# ecu.net
KiCad netlist of a schematic drawn in EAGLE
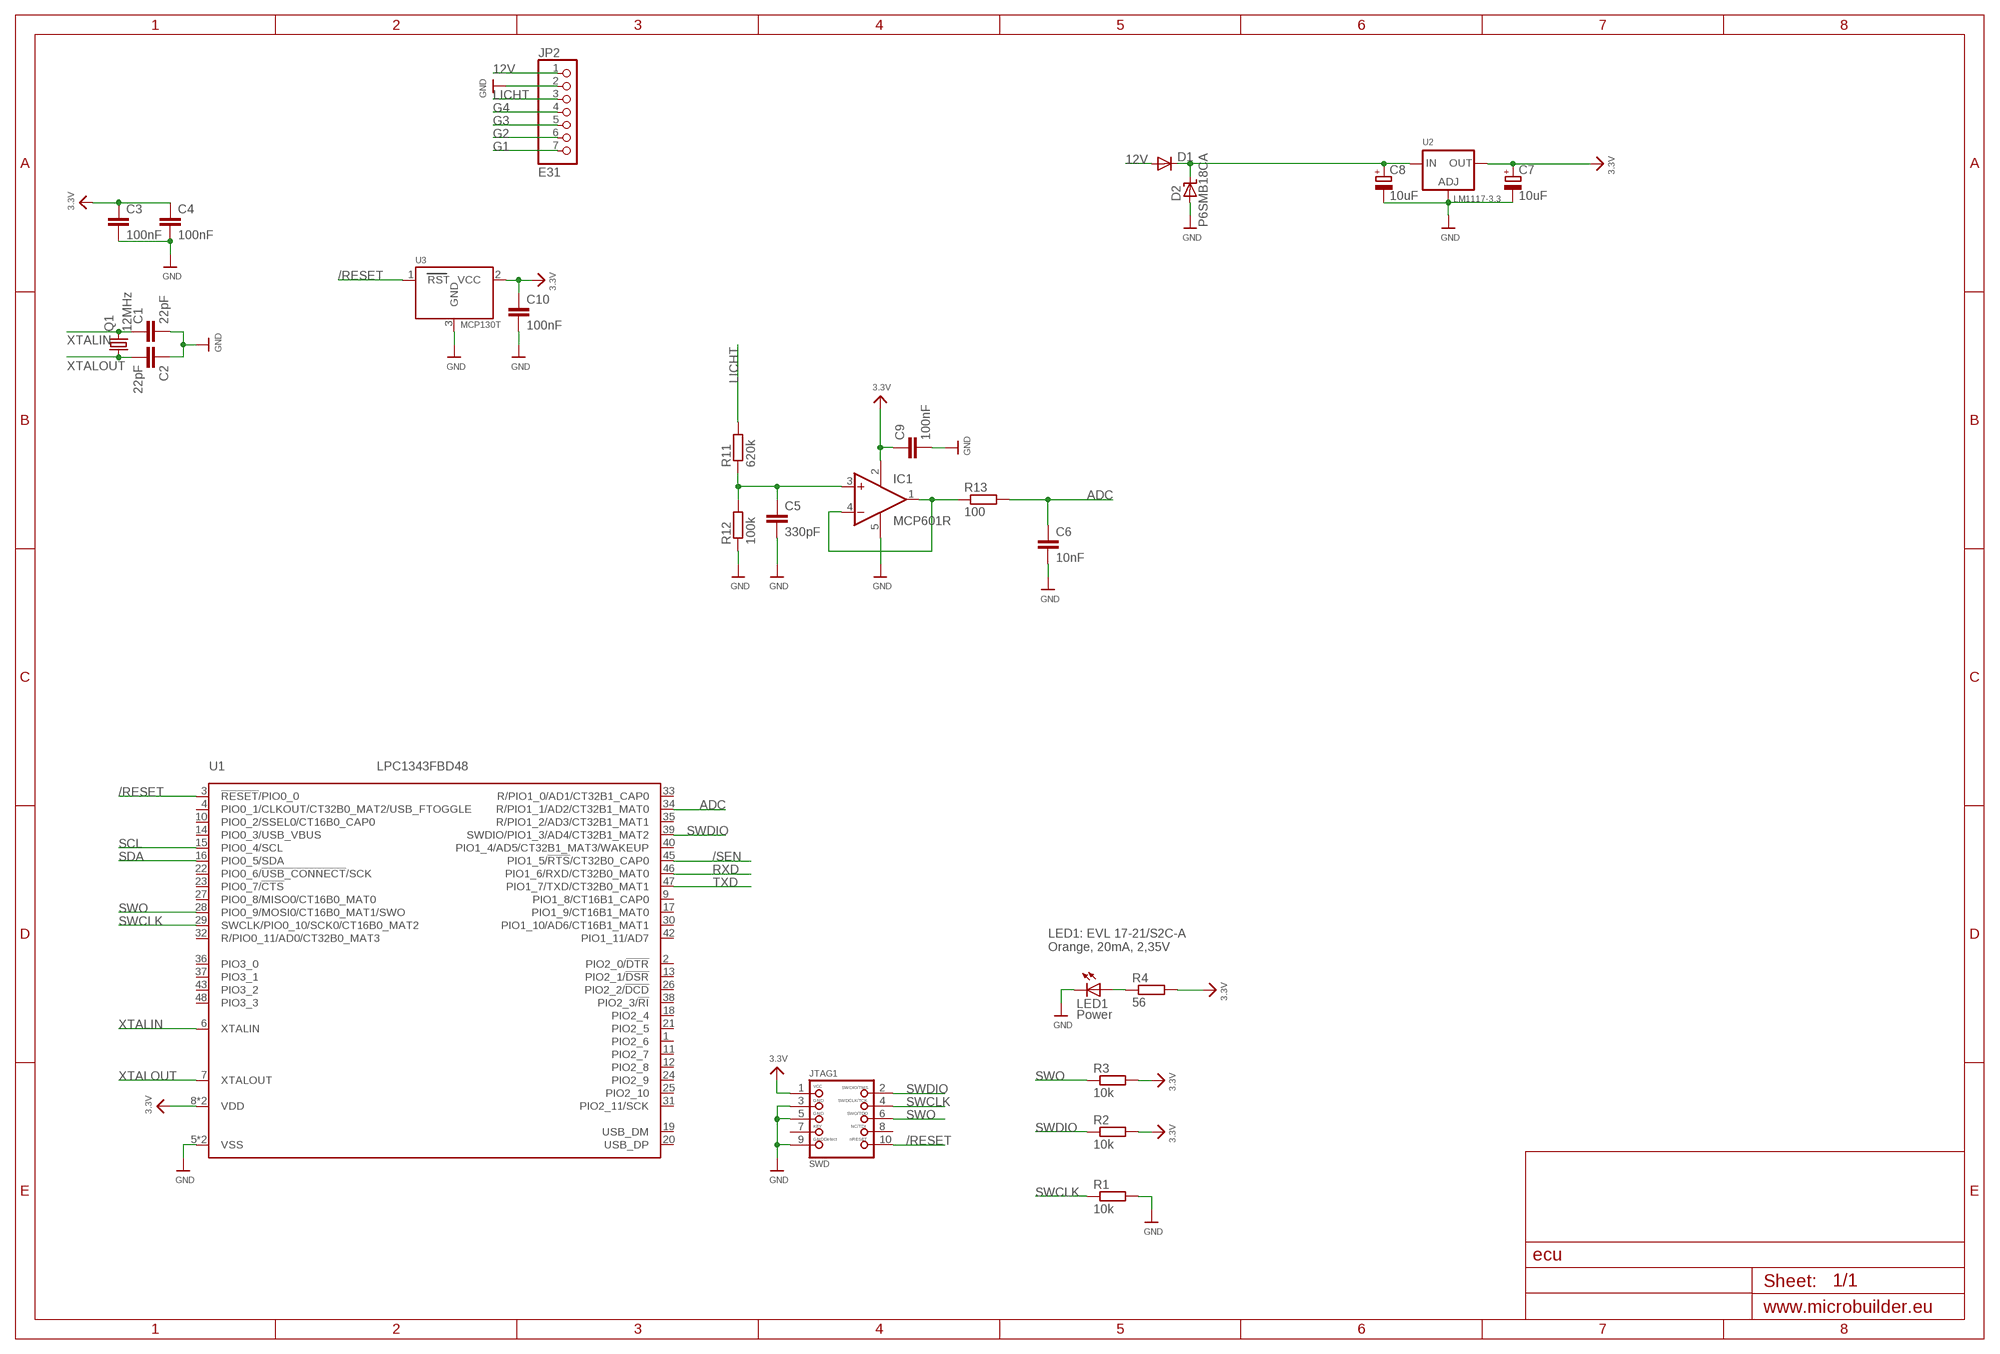
[diagram p0: schematic, sheet 1]

(export (version "E")
  (design (tool "Eeschema 10.0.6"))
  (components
    (comp (ref "C1")
      (value "22pF")
      (footprint "eagle-import:C0805")
      (libsource (lib "eagle-import") (part "C-EUC0805"))
    )
    (comp (ref "C2")
      (value "22pF")
      (footprint "eagle-import:C0805")
      (libsource (lib "eagle-import") (part "C-EUC0805"))
    )
    (comp (ref "C3")
      (value "100nF")
      (footprint "eagle-import:C0805")
      (libsource (lib "eagle-import") (part "C-EUC0805"))
    )
    (comp (ref "C4")
      (value "100nF")
      (footprint "eagle-import:C0805")
      (libsource (lib "eagle-import") (part "C-EUC0805"))
    )
    (comp (ref "C5")
      (value "330pF")
      (footprint "eagle-import:C0805")
      (libsource (lib "eagle-import") (part "C-EUC0805"))
    )
    (comp (ref "C6")
      (value "10nF")
      (footprint "eagle-import:C0805")
      (libsource (lib "eagle-import") (part "C-EUC0805"))
    )
    (comp (ref "C7")
      (value "10uF")
      (footprint "eagle-import:SMC_C")
      (libsource (lib "eagle-import") (part "CPOL-EUSMCC"))
    )
    (comp (ref "C8")
      (value "10uF")
      (footprint "eagle-import:SMC_C")
      (libsource (lib "eagle-import") (part "CPOL-EUSMCC"))
    )
    (comp (ref "C9")
      (value "100nF")
      (footprint "eagle-import:C0805")
      (libsource (lib "eagle-import") (part "rcl_334_C-EUC0805"))
    )
    (comp (ref "C10")
      (value "100nF")
      (footprint "eagle-import:C0805")
      (libsource (lib "eagle-import") (part "rcl_334_C-EUC0805"))
    )
    (comp (ref "D1")
      (value "DIODE-SMB")
      (footprint "eagle-import:SMB")
      (libsource (lib "eagle-import") (part "DIODE-SMB"))
    )
    (comp (ref "D2")
      (value "P6SMB18CA")
      (footprint "eagle-import:DO214AA")
      (libsource (lib "eagle-import") (part "SHOTKY-SMDSMB"))
    )
    (comp (ref "IC1")
      (value "MCP601R")
      (footprint "eagle-import:SOT23-5")
      (libsource (lib "eagle-import") (part "MCP601R"))
    )
    (comp (ref "JP2")
      (value "E31")
      (footprint "eagle-import:1X07_ROUND")
      (libsource (lib "eagle-import") (part "HEADER-1X7ROUND"))
    )
    (comp (ref "JTAG1")
      (value "SWD")
      (footprint "eagle-import:2X05_1.27MM_SMT")
      (libsource (lib "eagle-import") (part "JTAG-CORTEXM3"))
    )
    (comp (ref "LED1")
      (value "Power")
      (footprint "eagle-import:SML0805")
      (libsource (lib "eagle-import") (part "LEDSML0805"))
    )
    (comp (ref "Q1")
      (value "12MHz")
      (footprint "eagle-import:HC49UP")
      (libsource (lib "eagle-import") (part "CRYSTALHC49UP"))
    )
    (comp (ref "R1")
      (value "10k")
      (footprint "eagle-import:R0805")
      (libsource (lib "eagle-import") (part "rcl_334_R-EU_R0805"))
    )
    (comp (ref "R2")
      (value "10k")
      (footprint "eagle-import:R0805")
      (libsource (lib "eagle-import") (part "rcl_334_R-EU_R0805"))
    )
    (comp (ref "R3")
      (value "10k")
      (footprint "eagle-import:R0805")
      (libsource (lib "eagle-import") (part "rcl_334_R-EU_R0805"))
    )
    (comp (ref "R4")
      (value "56")
      (footprint "eagle-import:R0805")
      (libsource (lib "eagle-import") (part "rcl_334_R-EU_R0805"))
    )
    (comp (ref "R11")
      (value "620k")
      (footprint "eagle-import:R0805")
      (libsource (lib "eagle-import") (part "R-EU_R0805"))
    )
    (comp (ref "R12")
      (value "100k")
      (footprint "eagle-import:R0805")
      (libsource (lib "eagle-import") (part "R-EU_R0805"))
    )
    (comp (ref "R13")
      (value "100")
      (footprint "eagle-import:R0805")
      (libsource (lib "eagle-import") (part "R-EU_R0805"))
    )
    (comp (ref "U1")
      (value "LPC1343FBD48")
      (footprint "eagle-import:SOT313-2")
      (libsource (lib "eagle-import") (part "LPC1343FBD48"))
    )
    (comp (ref "U2")
      (value "LM1117-3.3")
      (footprint "eagle-import:SOT223-R")
      (libsource (lib "eagle-import") (part "LM1117SOT223-REFLOW"))
    )
    (comp (ref "U3")
      (value "MCP130T")
      (footprint "eagle-import:SOT23-W")
      (libsource (lib "eagle-import") (part "MCP130TWAVE"))
    )
  )
  (nets
    (net (code "1") (name "/12V") (class "Default")
      (node (ref "D1") (pin "A") (pinfunction "A_A") (pintype "passive"))
      (node (ref "JP2") (pin "1") (pinfunction "1_1") (pintype "passive"))
    )
    (net (code "2") (name "/ADC") (class "Default")
      (node (ref "C6") (pin "1") (pinfunction "1_1") (pintype "passive"))
      (node (ref "R13") (pin "2") (pinfunction "2_2") (pintype "passive"))
      (node (ref "U1") (pin "34") (pinfunction "R/PIO1_1/AD2/CT32B1_MAT0_34") (pintype "bidirectional"))
    )
    (net (code "3") (name "/G1") (class "Default")
      (node (ref "JP2") (pin "7") (pinfunction "7_7") (pintype "passive"))
    )
    (net (code "4") (name "/G2") (class "Default")
      (node (ref "JP2") (pin "6") (pinfunction "6_6") (pintype "passive"))
    )
    (net (code "5") (name "/G3") (class "Default")
      (node (ref "JP2") (pin "5") (pinfunction "5_5") (pintype "passive"))
    )
    (net (code "6") (name "/G4") (class "Default")
      (node (ref "JP2") (pin "4") (pinfunction "4_4") (pintype "passive"))
    )
    (net (code "7") (name "/LICHT") (class "Default")
      (node (ref "JP2") (pin "3") (pinfunction "3_3") (pintype "passive"))
      (node (ref "R11") (pin "2") (pinfunction "2_2") (pintype "passive"))
    )
    (net (code "8") (name "/RXD") (class "Default")
      (node (ref "U1") (pin "46") (pinfunction "PIO1_6/RXD/CT32B0_MAT0_46") (pintype "bidirectional"))
    )
    (net (code "9") (name "/SCL") (class "Default")
      (node (ref "U1") (pin "15") (pinfunction "PIO0_4/SCL_15") (pintype "bidirectional"))
    )
    (net (code "10") (name "/SDA") (class "Default")
      (node (ref "U1") (pin "16") (pinfunction "PIO0_5/SDA_16") (pintype "bidirectional"))
    )
    (net (code "11") (name "/SWCLK") (class "Default")
      (node (ref "JTAG1") (pin "4") (pinfunction "4_4") (pintype "passive"))
      (node (ref "R1") (pin "1") (pinfunction "1_1") (pintype "passive"))
      (node (ref "U1") (pin "29") (pinfunction "SWCLK/PIO0_10/SCK0/CT16B0_MAT2_29") (pintype "bidirectional"))
    )
    (net (code "12") (name "/SWDIO") (class "Default")
      (node (ref "JTAG1") (pin "2") (pinfunction "2_2") (pintype "passive"))
      (node (ref "R2") (pin "1") (pinfunction "1_1") (pintype "passive"))
      (node (ref "U1") (pin "39") (pinfunction "SWDIO/PIO1_3/AD4/CT32B1_MAT2_39") (pintype "bidirectional"))
    )
    (net (code "13") (name "/SWO") (class "Default")
      (node (ref "JTAG1") (pin "6") (pinfunction "6_6") (pintype "passive"))
      (node (ref "R3") (pin "1") (pinfunction "1_1") (pintype "passive"))
      (node (ref "U1") (pin "28") (pinfunction "PIO0_9/MOSI0/CT16B0_MAT1/SWO_28") (pintype "bidirectional"))
    )
    (net (code "14") (name "/TXD") (class "Default")
      (node (ref "U1") (pin "47") (pinfunction "PIO1_7/TXD/CT32B0_MAT1_47") (pintype "bidirectional"))
    )
    (net (code "15") (name "/XTALIN") (class "Default")
      (node (ref "C1") (pin "1") (pinfunction "1_1") (pintype "passive"))
      (node (ref "Q1") (pin "2") (pinfunction "2_2") (pintype "passive"))
      (node (ref "U1") (pin "6") (pinfunction "XTALIN_6") (pintype "input"))
    )
    (net (code "16") (name "/XTALOUT") (class "Default")
      (node (ref "C2") (pin "2") (pinfunction "2_2") (pintype "passive"))
      (node (ref "Q1") (pin "1") (pinfunction "1_1") (pintype "passive"))
      (node (ref "U1") (pin "7") (pinfunction "XTALOUT_7") (pintype "output"))
    )
    (net (code "17") (name "/{slash}RESET") (class "Default")
      (node (ref "JTAG1") (pin "10") (pinfunction "10_10") (pintype "passive"))
      (node (ref "U1") (pin "3") (pinfunction "~{RESET}/PIO0_0_3") (pintype "bidirectional"))
      (node (ref "U3") (pin "1") (pinfunction "RST_1") (pintype "bidirectional"))
    )
    (net (code "18") (name "/{slash}SEN") (class "Default")
      (node (ref "U1") (pin "45") (pinfunction "PIO1_5/~{RTS}/CT32B0_CAP0_45") (pintype "bidirectional"))
    )
    (net (code "19") (name "3.3V") (class "Default")
      (node (ref "C10") (pin "1") (pinfunction "1_1") (pintype "passive"))
      (node (ref "C3") (pin "1") (pinfunction "1_1") (pintype "passive"))
      (node (ref "C4") (pin "1") (pinfunction "1_1") (pintype "passive"))
      (node (ref "C7") (pin "+") (pinfunction "+_+") (pintype "passive"))
      (node (ref "C9") (pin "1") (pinfunction "1_1") (pintype "passive"))
      (node (ref "IC1") (pin "2") (pinfunction "V+_2") (pintype "power_in"))
      (node (ref "JTAG1") (pin "1") (pinfunction "1_1") (pintype "passive"))
      (node (ref "R2") (pin "2") (pinfunction "2_2") (pintype "passive"))
      (node (ref "R3") (pin "2") (pinfunction "2_2") (pintype "passive"))
      (node (ref "R4") (pin "2") (pinfunction "2_2") (pintype "passive"))
      (node (ref "U1") (pin "44") (pinfunction "VDD_44") (pintype "power_in"))
      (node (ref "U1") (pin "8") (pinfunction "VDD_8") (pintype "power_in"))
      (node (ref "U2") (pin "2") (pinfunction "OUT_2") (pintype "passive"))
      (node (ref "U3") (pin "2") (pinfunction "VCC_2") (pintype "power_in"))
    )
    (net (code "20") (name "GND") (class "Default")
      (node (ref "C1") (pin "2") (pinfunction "2_2") (pintype "passive"))
      (node (ref "C10") (pin "2") (pinfunction "2_2") (pintype "passive"))
      (node (ref "C2") (pin "1") (pinfunction "1_1") (pintype "passive"))
      (node (ref "C3") (pin "2") (pinfunction "2_2") (pintype "passive"))
      (node (ref "C4") (pin "2") (pinfunction "2_2") (pintype "passive"))
      (node (ref "C5") (pin "2") (pinfunction "2_2") (pintype "passive"))
      (node (ref "C6") (pin "2") (pinfunction "2_2") (pintype "passive"))
      (node (ref "C7") (pin "-") (pinfunction "-_-") (pintype "passive"))
      (node (ref "C8") (pin "-") (pinfunction "-_-") (pintype "passive"))
      (node (ref "C9") (pin "2") (pinfunction "2_2") (pintype "passive"))
      (node (ref "D2") (pin "A") (pinfunction "A_A") (pintype "passive"))
      (node (ref "IC1") (pin "5") (pinfunction "V-_5") (pintype "power_in"))
      (node (ref "JP2") (pin "2") (pinfunction "2_2") (pintype "passive"))
      (node (ref "JTAG1") (pin "3") (pinfunction "3_3") (pintype "passive"))
      (node (ref "JTAG1") (pin "5") (pinfunction "5_5") (pintype "passive"))
      (node (ref "JTAG1") (pin "9") (pinfunction "9_9") (pintype "passive"))
      (node (ref "LED1") (pin "C") (pinfunction "C_C") (pintype "passive"))
      (node (ref "R1") (pin "2") (pinfunction "2_2") (pintype "passive"))
      (node (ref "R12") (pin "1") (pinfunction "1_1") (pintype "passive"))
      (node (ref "U1") (pin "41") (pinfunction "VSS_41") (pintype "power_in"))
      (node (ref "U1") (pin "5") (pinfunction "VSS_5") (pintype "power_in"))
      (node (ref "U2") (pin "1") (pinfunction "ADJ_1") (pintype "input"))
      (node (ref "U3") (pin "3") (pinfunction "GND_3") (pintype "power_in"))
    )
    (net (code "21") (name "Net-(IC1-+IN)") (class "Default")
      (node (ref "C5") (pin "1") (pinfunction "1_1") (pintype "passive"))
      (node (ref "IC1") (pin "3") (pinfunction "+IN_3") (pintype "input"))
      (node (ref "R11") (pin "1") (pinfunction "1_1") (pintype "passive"))
      (node (ref "R12") (pin "2") (pinfunction "2_2") (pintype "passive"))
    )
    (net (code "22") (name "Net-(IC1--IN)") (class "Default")
      (node (ref "IC1") (pin "1") (pinfunction "OUT_1") (pintype "output"))
      (node (ref "IC1") (pin "4") (pinfunction "-IN_4") (pintype "input"))
      (node (ref "R13") (pin "1") (pinfunction "1_1") (pintype "passive"))
    )
    (net (code "23") (name "Net-(LED1-PadA)") (class "Default")
      (node (ref "LED1") (pin "A") (pinfunction "A_A") (pintype "passive"))
      (node (ref "R4") (pin "1") (pinfunction "1_1") (pintype "passive"))
    )
    (net (code "24") (name "Net-(U2-IN)") (class "Default")
      (node (ref "C8") (pin "+") (pinfunction "+_+") (pintype "passive"))
      (node (ref "D1") (pin "C") (pinfunction "C_C") (pintype "passive"))
      (node (ref "D2") (pin "C") (pinfunction "C_C") (pintype "passive"))
      (node (ref "U2") (pin "3") (pinfunction "IN_3") (pintype "input"))
    )
    (net (code "25") (name "unconnected-(JTAG1-Pad7)") (class "Default")
      (node (ref "JTAG1") (pin "7") (pinfunction "7_7") (pintype "passive"))
    )
    (net (code "26") (name "unconnected-(JTAG1-Pad8)") (class "Default")
      (node (ref "JTAG1") (pin "8") (pinfunction "8_8") (pintype "passive"))
    )
    (net (code "27") (name "unconnected-(U1-PIO0_1{slash}CLKOUT{slash}CT32B0_MAT2{slash}USB_FTOGGLE-Pad4)") (class "Default")
      (node (ref "U1") (pin "4") (pinfunction "PIO0_1/CLKOUT/CT32B0_MAT2/USB_FTOGGLE_4") (pintype "bidirectional"))
    )
    (net (code "28") (name "unconnected-(U1-PIO0_2{slash}SSEL0{slash}CT16B0_CAP0-Pad10)") (class "Default")
      (node (ref "U1") (pin "10") (pinfunction "PIO0_2/SSEL0/CT16B0_CAP0_10") (pintype "bidirectional"))
    )
    (net (code "29") (name "unconnected-(U1-PIO0_3{slash}USB_VBUS-Pad14)") (class "Default")
      (node (ref "U1") (pin "14") (pinfunction "PIO0_3/USB_VBUS_14") (pintype "bidirectional"))
    )
    (net (code "30") (name "unconnected-(U1-PIO0_6{slash}~{USB_CONNECT}{slash}SCK-Pad22)") (class "Default")
      (node (ref "U1") (pin "22") (pinfunction "PIO0_6/~{USB_CONNECT}/SCK_22") (pintype "bidirectional"))
    )
    (net (code "31") (name "unconnected-(U1-PIO0_7{slash}~{CTS}-Pad23)") (class "Default")
      (node (ref "U1") (pin "23") (pinfunction "PIO0_7/~{CTS}_23") (pintype "bidirectional"))
    )
    (net (code "32") (name "unconnected-(U1-PIO0_8{slash}MISO0{slash}CT16B0_MAT0-Pad27)") (class "Default")
      (node (ref "U1") (pin "27") (pinfunction "PIO0_8/MISO0/CT16B0_MAT0_27") (pintype "bidirectional"))
    )
    (net (code "33") (name "unconnected-(U1-PIO1_4{slash}AD5{slash}CT32B1_MAT3{slash}WAKEUP-Pad40)") (class "Default")
      (node (ref "U1") (pin "40") (pinfunction "PIO1_4/AD5/CT32B1_MAT3/WAKEUP_40") (pintype "bidirectional"))
    )
    (net (code "34") (name "unconnected-(U1-PIO1_8{slash}CT16B1_CAP0-Pad9)") (class "Default")
      (node (ref "U1") (pin "9") (pinfunction "PIO1_8/CT16B1_CAP0_9") (pintype "bidirectional"))
    )
    (net (code "35") (name "unconnected-(U1-PIO1_9{slash}CT16B1_MAT0-Pad17)") (class "Default")
      (node (ref "U1") (pin "17") (pinfunction "PIO1_9/CT16B1_MAT0_17") (pintype "bidirectional"))
    )
    (net (code "36") (name "unconnected-(U1-PIO1_10{slash}AD6{slash}CT16B1_MAT1-Pad30)") (class "Default")
      (node (ref "U1") (pin "30") (pinfunction "PIO1_10/AD6/CT16B1_MAT1_30") (pintype "bidirectional"))
    )
    (net (code "37") (name "unconnected-(U1-PIO1_11{slash}AD7-Pad42)") (class "Default")
      (node (ref "U1") (pin "42") (pinfunction "PIO1_11/AD7_42") (pintype "bidirectional"))
    )
    (net (code "38") (name "unconnected-(U1-PIO2_0{slash}~{DTR}-Pad2)") (class "Default")
      (node (ref "U1") (pin "2") (pinfunction "PIO2_0/~{DTR}_2") (pintype "bidirectional"))
    )
    (net (code "39") (name "unconnected-(U1-PIO2_1{slash}~{DSR}-Pad13)") (class "Default")
      (node (ref "U1") (pin "13") (pinfunction "PIO2_1/~{DSR}_13") (pintype "bidirectional"))
    )
    (net (code "40") (name "unconnected-(U1-PIO2_2{slash}~{DCD}-Pad26)") (class "Default")
      (node (ref "U1") (pin "26") (pinfunction "PIO2_2/~{DCD}_26") (pintype "bidirectional"))
    )
    (net (code "41") (name "unconnected-(U1-PIO2_3{slash}~{RI}-Pad38)") (class "Default")
      (node (ref "U1") (pin "38") (pinfunction "PIO2_3/~{RI}_38") (pintype "bidirectional"))
    )
    (net (code "42") (name "unconnected-(U1-PIO2_4-Pad18)") (class "Default")
      (node (ref "U1") (pin "18") (pinfunction "PIO2_4_18") (pintype "bidirectional"))
    )
    (net (code "43") (name "unconnected-(U1-PIO2_5-Pad21)") (class "Default")
      (node (ref "U1") (pin "21") (pinfunction "PIO2_5_21") (pintype "bidirectional"))
    )
    (net (code "44") (name "unconnected-(U1-PIO2_6-Pad1)") (class "Default")
      (node (ref "U1") (pin "1") (pinfunction "PIO2_6_1") (pintype "bidirectional"))
    )
    (net (code "45") (name "unconnected-(U1-PIO2_7-Pad11)") (class "Default")
      (node (ref "U1") (pin "11") (pinfunction "PIO2_7_11") (pintype "bidirectional"))
    )
    (net (code "46") (name "unconnected-(U1-PIO2_8-Pad12)") (class "Default")
      (node (ref "U1") (pin "12") (pinfunction "PIO2_8_12") (pintype "bidirectional"))
    )
    (net (code "47") (name "unconnected-(U1-PIO2_9-Pad24)") (class "Default")
      (node (ref "U1") (pin "24") (pinfunction "PIO2_9_24") (pintype "bidirectional"))
    )
    (net (code "48") (name "unconnected-(U1-PIO2_10-Pad25)") (class "Default")
      (node (ref "U1") (pin "25") (pinfunction "PIO2_10_25") (pintype "bidirectional"))
    )
    (net (code "49") (name "unconnected-(U1-PIO2_11{slash}SCK-Pad31)") (class "Default")
      (node (ref "U1") (pin "31") (pinfunction "PIO2_11/SCK_31") (pintype "bidirectional"))
    )
    (net (code "50") (name "unconnected-(U1-PIO3_0-Pad36)") (class "Default")
      (node (ref "U1") (pin "36") (pinfunction "PIO3_0_36") (pintype "bidirectional"))
    )
    (net (code "51") (name "unconnected-(U1-PIO3_1-Pad37)") (class "Default")
      (node (ref "U1") (pin "37") (pinfunction "PIO3_1_37") (pintype "bidirectional"))
    )
    (net (code "52") (name "unconnected-(U1-PIO3_2-Pad43)") (class "Default")
      (node (ref "U1") (pin "43") (pinfunction "PIO3_2_43") (pintype "bidirectional"))
    )
    (net (code "53") (name "unconnected-(U1-PIO3_3-Pad48)") (class "Default")
      (node (ref "U1") (pin "48") (pinfunction "PIO3_3_48") (pintype "bidirectional"))
    )
    (net (code "54") (name "unconnected-(U1-R{slash}PIO0_11{slash}AD0{slash}CT32B0_MAT3-Pad32)") (class "Default")
      (node (ref "U1") (pin "32") (pinfunction "R/PIO0_11/AD0/CT32B0_MAT3_32") (pintype "bidirectional"))
    )
    (net (code "55") (name "unconnected-(U1-R{slash}PIO1_0{slash}AD1{slash}CT32B1_CAP0-Pad33)") (class "Default")
      (node (ref "U1") (pin "33") (pinfunction "R/PIO1_0/AD1/CT32B1_CAP0_33") (pintype "bidirectional"))
    )
    (net (code "56") (name "unconnected-(U1-R{slash}PIO1_2{slash}AD3{slash}CT32B1_MAT1-Pad35)") (class "Default")
      (node (ref "U1") (pin "35") (pinfunction "R/PIO1_2/AD3/CT32B1_MAT1_35") (pintype "bidirectional"))
    )
    (net (code "57") (name "unconnected-(U1-USB_DM-Pad19)") (class "Default")
      (node (ref "U1") (pin "19") (pinfunction "USB_DM_19") (pintype "bidirectional"))
    )
    (net (code "58") (name "unconnected-(U1-USB_DP-Pad20)") (class "Default")
      (node (ref "U1") (pin "20") (pinfunction "USB_DP_20") (pintype "bidirectional"))
    )
  )
)
